# top_PCB.net
KiCad netlist of a schematic drawn in EAGLE
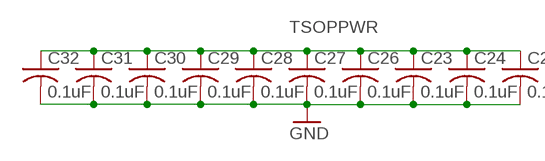
[diagram p0: schematic, sheet 1, part 1 of 2]
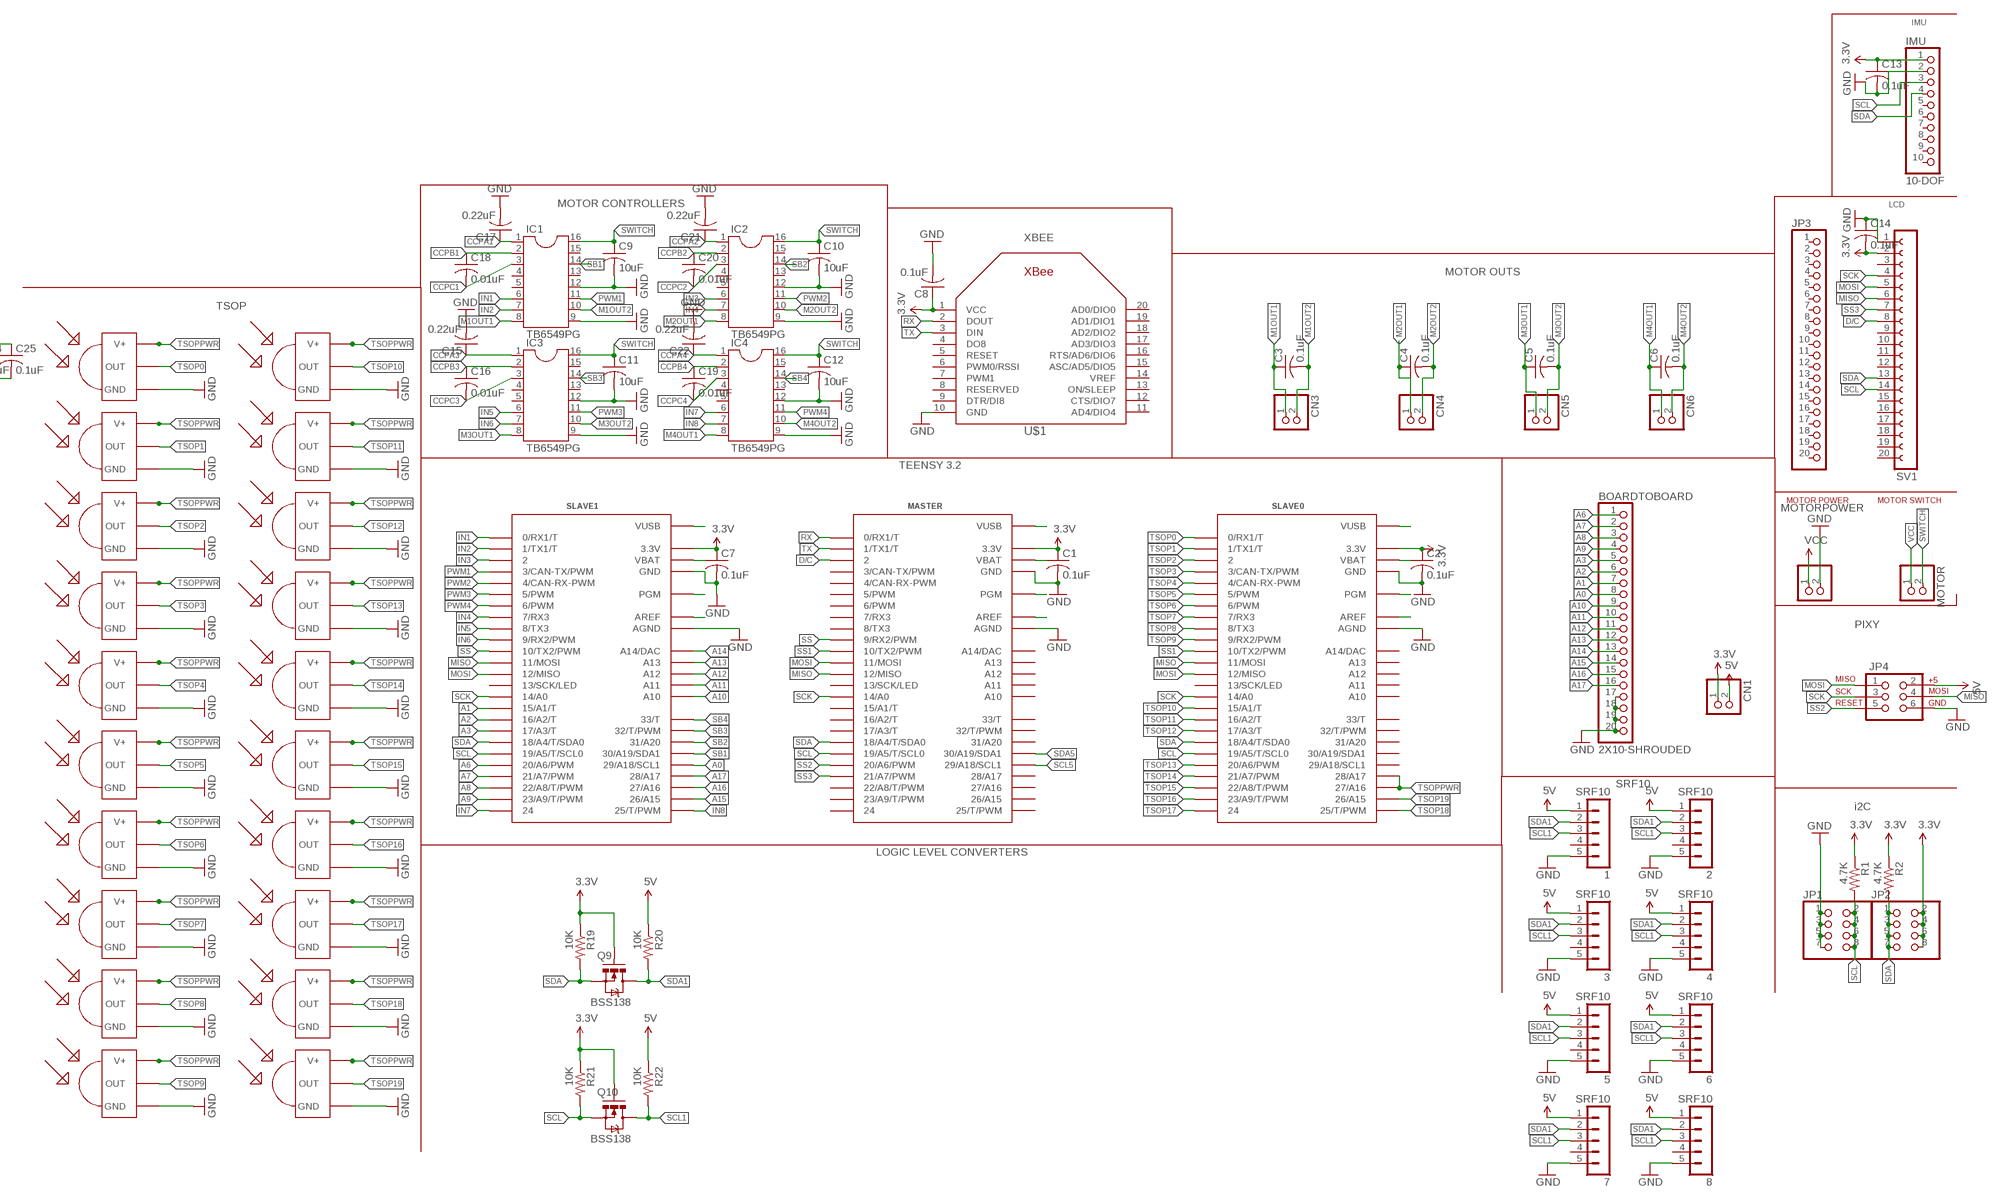
[diagram p1: schematic, sheet 1, part 2 of 2]

(export (version "E")
  (design (tool "Eeschema 10.0.6"))
  (components
    (comp (ref "1")
      (value "SRF10")
      (footprint "eagle-import:MA05-1")
      (libsource (lib "eagle-import") (part "MA05-1"))
    )
    (comp (ref "2")
      (value "SRF10")
      (footprint "eagle-import:MA05-1")
      (libsource (lib "eagle-import") (part "MA05-1"))
    )
    (comp (ref "3")
      (value "SRF10")
      (footprint "eagle-import:MA05-1")
      (libsource (lib "eagle-import") (part "MA05-1"))
    )
    (comp (ref "4")
      (value "SRF10")
      (footprint "eagle-import:MA05-1")
      (libsource (lib "eagle-import") (part "MA05-1"))
    )
    (comp (ref "5")
      (value "SRF10")
      (footprint "eagle-import:MA05-1")
      (libsource (lib "eagle-import") (part "MA05-1"))
    )
    (comp (ref "6")
      (value "SRF10")
      (footprint "eagle-import:MA05-1")
      (libsource (lib "eagle-import") (part "MA05-1"))
    )
    (comp (ref "7")
      (value "SRF10")
      (footprint "eagle-import:MA05-1")
      (libsource (lib "eagle-import") (part "MA05-1"))
    )
    (comp (ref "8")
      (value "SRF10")
      (footprint "eagle-import:MA05-1")
      (libsource (lib "eagle-import") (part "MA05-1"))
    )
    (comp (ref "BOARDTOBOARD")
      (value "2X10-SHROUDED")
      (footprint "eagle-import:2X10-SHROUDED")
      (libsource (lib "eagle-import") (part "2X10-SHROUDED"))
    )
    (comp (ref "C1")
      (value "0.1uF")
      (footprint "eagle-import:C0805")
      (libsource (lib "eagle-import") (part "C-USC0805"))
    )
    (comp (ref "C2")
      (value "0.1uF")
      (footprint "eagle-import:C0805")
      (libsource (lib "eagle-import") (part "C-USC0805"))
    )
    (comp (ref "C3")
      (value "0.1uF")
      (footprint "eagle-import:C0805")
      (libsource (lib "eagle-import") (part "C-USC0805"))
    )
    (comp (ref "C4")
      (value "0.1uF")
      (footprint "eagle-import:C0805")
      (libsource (lib "eagle-import") (part "C-USC0805"))
    )
    (comp (ref "C5")
      (value "0.1uF")
      (footprint "eagle-import:C0805")
      (libsource (lib "eagle-import") (part "C-USC0805"))
    )
    (comp (ref "C6")
      (value "0.1uF")
      (footprint "eagle-import:C0805")
      (libsource (lib "eagle-import") (part "C-USC0805"))
    )
    (comp (ref "C7")
      (value "0.1uF")
      (footprint "eagle-import:C0805")
      (libsource (lib "eagle-import") (part "C-USC0805"))
    )
    (comp (ref "C8")
      (value "0.1uF")
      (footprint "eagle-import:C0805")
      (libsource (lib "eagle-import") (part "C-USC0805"))
    )
    (comp (ref "C9")
      (value "10uF")
      (footprint "eagle-import:C0805")
      (libsource (lib "eagle-import") (part "C-USC0805"))
    )
    (comp (ref "C10")
      (value "10uF")
      (footprint "eagle-import:C0805")
      (libsource (lib "eagle-import") (part "C-USC0805"))
    )
    (comp (ref "C11")
      (value "10uF")
      (footprint "eagle-import:C0805")
      (libsource (lib "eagle-import") (part "C-USC0805"))
    )
    (comp (ref "C12")
      (value "10uF")
      (footprint "eagle-import:C0805")
      (libsource (lib "eagle-import") (part "C-USC0805"))
    )
    (comp (ref "C13")
      (value "0.1uF")
      (footprint "eagle-import:C0805")
      (libsource (lib "eagle-import") (part "C-USC0805"))
    )
    (comp (ref "C14")
      (value "0.1uF")
      (footprint "eagle-import:C0805")
      (libsource (lib "eagle-import") (part "C-USC0805"))
    )
    (comp (ref "C15")
      (value "0.22uF")
      (footprint "eagle-import:C0805")
      (libsource (lib "eagle-import") (part "C-USC0805"))
    )
    (comp (ref "C16")
      (value "0.01uF")
      (footprint "eagle-import:C0805")
      (libsource (lib "eagle-import") (part "C-USC0805"))
    )
    (comp (ref "C17")
      (value "0.22uF")
      (footprint "eagle-import:C0805")
      (libsource (lib "eagle-import") (part "C-USC0805"))
    )
    (comp (ref "C18")
      (value "0.01uF")
      (footprint "eagle-import:C0805")
      (libsource (lib "eagle-import") (part "C-USC0805"))
    )
    (comp (ref "C19")
      (value "0.01uF")
      (footprint "eagle-import:C0805")
      (libsource (lib "eagle-import") (part "C-USC0805"))
    )
    (comp (ref "C20")
      (value "0.01uF")
      (footprint "eagle-import:C0805")
      (libsource (lib "eagle-import") (part "C-USC0805"))
    )
    (comp (ref "C21")
      (value "0.22uF")
      (footprint "eagle-import:C0805")
      (libsource (lib "eagle-import") (part "C-USC0805"))
    )
    (comp (ref "C22")
      (value "0.22uF")
      (footprint "eagle-import:C0805")
      (libsource (lib "eagle-import") (part "C-USC0805"))
    )
    (comp (ref "C23")
      (value "0.1uF")
      (footprint "eagle-import:C0805")
      (libsource (lib "eagle-import") (part "C-USC0805"))
    )
    (comp (ref "C24")
      (value "0.1uF")
      (footprint "eagle-import:C0805")
      (libsource (lib "eagle-import") (part "C-USC0805"))
    )
    (comp (ref "C25")
      (value "0.1uF")
      (footprint "eagle-import:C0805")
      (libsource (lib "eagle-import") (part "C-USC0805"))
    )
    (comp (ref "C26")
      (value "0.1uF")
      (footprint "eagle-import:C0805")
      (libsource (lib "eagle-import") (part "C-USC0805"))
    )
    (comp (ref "C27")
      (value "0.1uF")
      (footprint "eagle-import:C0805")
      (libsource (lib "eagle-import") (part "C-USC0805"))
    )
    (comp (ref "C28")
      (value "0.1uF")
      (footprint "eagle-import:C0805")
      (libsource (lib "eagle-import") (part "C-USC0805"))
    )
    (comp (ref "C29")
      (value "0.1uF")
      (footprint "eagle-import:C0805")
      (libsource (lib "eagle-import") (part "C-USC0805"))
    )
    (comp (ref "C30")
      (value "0.1uF")
      (footprint "eagle-import:C0805")
      (libsource (lib "eagle-import") (part "C-USC0805"))
    )
    (comp (ref "C31")
      (value "0.1uF")
      (footprint "eagle-import:C0805")
      (libsource (lib "eagle-import") (part "C-USC0805"))
    )
    (comp (ref "C32")
      (value "0.1uF")
      (footprint "eagle-import:C0805")
      (libsource (lib "eagle-import") (part "C-USC0805"))
    )
    (comp (ref "CN1")
      (value "JST_2PIN-SMT")
      (footprint "eagle-import:JST-PH-2-SMT")
      (libsource (lib "eagle-import") (part "JST_2PIN-SMT"))
    )
    (comp (ref "CN3")
      (value "JST_2PIN-SMT")
      (footprint "eagle-import:JST-PH-2-SMT")
      (libsource (lib "eagle-import") (part "JST_2PIN-SMT"))
    )
    (comp (ref "CN4")
      (value "JST_2PIN-SMT")
      (footprint "eagle-import:JST-PH-2-SMT")
      (libsource (lib "eagle-import") (part "JST_2PIN-SMT"))
    )
    (comp (ref "CN5")
      (value "JST_2PIN-SMT")
      (footprint "eagle-import:JST-PH-2-SMT")
      (libsource (lib "eagle-import") (part "JST_2PIN-SMT"))
    )
    (comp (ref "CN6")
      (value "JST_2PIN-SMT")
      (footprint "eagle-import:JST-PH-2-SMT")
      (libsource (lib "eagle-import") (part "JST_2PIN-SMT"))
    )
    (comp (ref "IC1")
      (value "TB6549PG")
      (footprint "eagle-import:DIL16")
      (libsource (lib "eagle-import") (part "DIL16"))
    )
    (comp (ref "IC2")
      (value "TB6549PG")
      (footprint "eagle-import:DIL16")
      (libsource (lib "eagle-import") (part "DIL16"))
    )
    (comp (ref "IC3")
      (value "TB6549PG")
      (footprint "eagle-import:DIL16")
      (libsource (lib "eagle-import") (part "DIL16"))
    )
    (comp (ref "IC4")
      (value "TB6549PG")
      (footprint "eagle-import:DIL16")
      (libsource (lib "eagle-import") (part "DIL16"))
    )
    (comp (ref "IMU")
      (value "10-DOF")
      (footprint "eagle-import:1X10-BIG")
      (libsource (lib "eagle-import") (part "PINHD-1X10"))
    )
    (comp (ref "JP1")
      (value "PINHD-2X4")
      (footprint "eagle-import:2X04")
      (libsource (lib "eagle-import") (part "PINHD-2X4"))
    )
    (comp (ref "JP2")
      (value "PINHD-2X4")
      (footprint "eagle-import:2X04")
      (libsource (lib "eagle-import") (part "PINHD-2X4"))
    )
    (comp (ref "JP3")
      (value "PINHD-1X20")
      (footprint "eagle-import:1X20")
      (libsource (lib "eagle-import") (part "PINHD-1X20"))
    )
    (comp (ref "JP4")
      (value "AVR_SPI_PRG_6PTH")
      (footprint "eagle-import:2X3")
      (libsource (lib "eagle-import") (part "AVR_SPI_PRG_6PTH"))
    )
    (comp (ref "MASTER")
      (value "TEENSY_3.1_ALL_PINS_AND_PADS-VIN")
      (footprint "eagle-import:TEENSY_3.1_ALLPINS-VIN")
      (libsource (lib "eagle-import") (part "TEENSY_3.1_ALL_PINS_AND_PADS-VIN"))
    )
    (comp (ref "MOTOR")
      (value "JST_2PIN-SMT")
      (footprint "eagle-import:JST-PH-2-SMT")
      (libsource (lib "eagle-import") (part "JST_2PIN-SMT"))
    )
    (comp (ref "MOTORPOWER")
      (value "JST_2PIN-SMT")
      (footprint "eagle-import:JST-PH-2-SMT")
      (libsource (lib "eagle-import") (part "JST_2PIN-SMT"))
    )
    (comp (ref "Q9")
      (value "BSS138")
      (footprint "eagle-import:SOT23-3")
      (libsource (lib "eagle-import") (part "MOSFET-NCHANNELSMD"))
    )
    (comp (ref "Q10")
      (value "BSS138")
      (footprint "eagle-import:SOT23-3")
      (libsource (lib "eagle-import") (part "MOSFET-NCHANNELSMD"))
    )
    (comp (ref "R1")
      (value "4.7K")
      (footprint "eagle-import:R0805")
      (libsource (lib "eagle-import") (part "R-US_R0805"))
    )
    (comp (ref "R2")
      (value "4.7K")
      (footprint "eagle-import:R0805")
      (libsource (lib "eagle-import") (part "R-US_R0805"))
    )
    (comp (ref "R19")
      (value "10K")
      (footprint "eagle-import:0603-RES")
      (libsource (lib "eagle-import") (part "RESISTOR0603-RES"))
    )
    (comp (ref "R20")
      (value "10K")
      (footprint "eagle-import:0603-RES")
      (libsource (lib "eagle-import") (part "RESISTOR0603-RES"))
    )
    (comp (ref "R21")
      (value "10K")
      (footprint "eagle-import:0603-RES")
      (libsource (lib "eagle-import") (part "RESISTOR0603-RES"))
    )
    (comp (ref "R22")
      (value "10K")
      (footprint "eagle-import:0603-RES")
      (libsource (lib "eagle-import") (part "RESISTOR0603-RES"))
    )
    (comp (ref "SLAVE0")
      (value "TEENSY_3.1_ALL_PINS_AND_PADS-VIN")
      (footprint "eagle-import:TEENSY_3.1_ALLPINS-VIN")
      (libsource (lib "eagle-import") (part "TEENSY_3.1_ALL_PINS_AND_PADS-VIN"))
    )
    (comp (ref "SLAVE1")
      (value "TEENSY_3.1_ALL_PINS_AND_PADS-VIN")
      (footprint "eagle-import:TEENSY_3.1_ALLPINS-VIN")
      (libsource (lib "eagle-import") (part "TEENSY_3.1_ALL_PINS_AND_PADS-VIN"))
    )
    (comp (ref "SV1")
      (value "FE20-1")
      (footprint "eagle-import:FE20")
      (libsource (lib "eagle-import") (part "FE20-1"))
    )
    (comp (ref "TSOP1")
      (value "TSOP1730")
      (footprint "eagle-import:TSOP17XX")
      (libsource (lib "eagle-import") (part "TSOP1730"))
    )
    (comp (ref "TSOP2")
      (value "TSOP1730")
      (footprint "eagle-import:TSOP17XX")
      (libsource (lib "eagle-import") (part "TSOP1730"))
    )
    (comp (ref "TSOP3")
      (value "TSOP1730")
      (footprint "eagle-import:TSOP17XX")
      (libsource (lib "eagle-import") (part "TSOP1730"))
    )
    (comp (ref "TSOP4")
      (value "TSOP1730")
      (footprint "eagle-import:TSOP17XX")
      (libsource (lib "eagle-import") (part "TSOP1730"))
    )
    (comp (ref "TSOP5")
      (value "TSOP1730")
      (footprint "eagle-import:TSOP17XX")
      (libsource (lib "eagle-import") (part "TSOP1730"))
    )
    (comp (ref "TSOP6")
      (value "TSOP1730")
      (footprint "eagle-import:TSOP17XX")
      (libsource (lib "eagle-import") (part "TSOP1730"))
    )
    (comp (ref "TSOP7")
      (value "TSOP1730")
      (footprint "eagle-import:TSOP17XX")
      (libsource (lib "eagle-import") (part "TSOP1730"))
    )
    (comp (ref "TSOP8")
      (value "TSOP1730")
      (footprint "eagle-import:TSOP17XX")
      (libsource (lib "eagle-import") (part "TSOP1730"))
    )
    (comp (ref "TSOP9")
      (value "TSOP1730")
      (footprint "eagle-import:TSOP17XX")
      (libsource (lib "eagle-import") (part "TSOP1730"))
    )
    (comp (ref "TSOP10")
      (value "TSOP1730")
      (footprint "eagle-import:TSOP17XX")
      (libsource (lib "eagle-import") (part "TSOP1730"))
    )
    (comp (ref "TSOP11")
      (value "TSOP1730")
      (footprint "eagle-import:TSOP17XX")
      (libsource (lib "eagle-import") (part "TSOP1730"))
    )
    (comp (ref "TSOP12")
      (value "TSOP1730")
      (footprint "eagle-import:TSOP17XX")
      (libsource (lib "eagle-import") (part "TSOP1730"))
    )
    (comp (ref "TSOP13")
      (value "TSOP1730")
      (footprint "eagle-import:TSOP17XX")
      (libsource (lib "eagle-import") (part "TSOP1730"))
    )
    (comp (ref "TSOP14")
      (value "TSOP1730")
      (footprint "eagle-import:TSOP17XX")
      (libsource (lib "eagle-import") (part "TSOP1730"))
    )
    (comp (ref "TSOP15")
      (value "TSOP1730")
      (footprint "eagle-import:TSOP17XX")
      (libsource (lib "eagle-import") (part "TSOP1730"))
    )
    (comp (ref "TSOP16")
      (value "TSOP1730")
      (footprint "eagle-import:TSOP17XX")
      (libsource (lib "eagle-import") (part "TSOP1730"))
    )
    (comp (ref "TSOP17")
      (value "TSOP1730")
      (footprint "eagle-import:TSOP17XX")
      (libsource (lib "eagle-import") (part "TSOP1730"))
    )
    (comp (ref "TSOP18")
      (value "TSOP1730")
      (footprint "eagle-import:TSOP17XX")
      (libsource (lib "eagle-import") (part "TSOP1730"))
    )
    (comp (ref "TSOP19")
      (value "TSOP1730")
      (footprint "eagle-import:TSOP17XX")
      (libsource (lib "eagle-import") (part "TSOP1730"))
    )
    (comp (ref "TSOP20")
      (value "TSOP1730")
      (footprint "eagle-import:TSOP17XX")
      (libsource (lib "eagle-import") (part "TSOP1730"))
    )
    (comp (ref "U$1")
      (value "XBEE")
      (footprint "eagle-import:XBEE")
      (libsource (lib "eagle-import") (part "XBEE"))
    )
  )
  (nets
    (net (code "1") (name "3.3V") (class "Default")
      (node (ref "C1") (pin "1") (pinfunction "1_1") (pintype "passive"))
      (node (ref "C13") (pin "1") (pinfunction "1_1") (pintype "passive"))
      (node (ref "C14") (pin "2") (pinfunction "2_2") (pintype "passive"))
      (node (ref "C2") (pin "1") (pinfunction "1_1") (pintype "passive"))
      (node (ref "C7") (pin "1") (pinfunction "1_1") (pintype "passive"))
      (node (ref "C8") (pin "1") (pinfunction "1_1") (pintype "passive"))
      (node (ref "CN1") (pin "1") (pinfunction "2_1") (pintype "passive"))
      (node (ref "IMU") (pin "1") (pinfunction "1_1") (pintype "passive"))
      (node (ref "JP2") (pin "2") (pinfunction "2_2") (pintype "passive"))
      (node (ref "JP2") (pin "4") (pinfunction "4_4") (pintype "passive"))
      (node (ref "JP2") (pin "6") (pinfunction "6_6") (pintype "passive"))
      (node (ref "JP2") (pin "8") (pinfunction "8_8") (pintype "passive"))
      (node (ref "MASTER") (pin "3.3V") (pinfunction "3.3V_3.3V") (pintype "power_in"))
      (node (ref "MASTER") (pin "3.3V1") (pinfunction "3.3V_3.3V1") (pintype "power_in"))
      (node (ref "MASTER") (pin "3.3V2") (pinfunction "3.3V_3.3V2") (pintype "power_in"))
      (node (ref "Q10") (pin "1") (pinfunction "G_1") (pintype "passive"))
      (node (ref "Q9") (pin "1") (pinfunction "G_1") (pintype "passive"))
      (node (ref "R1") (pin "1") (pinfunction "1_1") (pintype "passive"))
      (node (ref "R19") (pin "1") (pinfunction "1_1") (pintype "passive"))
      (node (ref "R2") (pin "1") (pinfunction "1_1") (pintype "passive"))
      (node (ref "R21") (pin "1") (pinfunction "1_1") (pintype "passive"))
      (node (ref "SLAVE0") (pin "3.3V") (pinfunction "3.3V_3.3V") (pintype "power_in"))
      (node (ref "SLAVE0") (pin "3.3V1") (pinfunction "3.3V_3.3V1") (pintype "power_in"))
      (node (ref "SLAVE0") (pin "3.3V2") (pinfunction "3.3V_3.3V2") (pintype "power_in"))
      (node (ref "SLAVE1") (pin "3.3V") (pinfunction "3.3V_3.3V") (pintype "power_in"))
      (node (ref "SLAVE1") (pin "3.3V1") (pinfunction "3.3V_3.3V1") (pintype "power_in"))
      (node (ref "SLAVE1") (pin "3.3V2") (pinfunction "3.3V_3.3V2") (pintype "power_in"))
      (node (ref "SV1") (pin "2") (pinfunction "2_2") (pintype "passive"))
      (node (ref "U$1") (pin "1") (pinfunction "VCC_1") (pintype "power_in"))
    )
    (net (code "2") (name "5V") (class "Default")
      (node (ref "1") (pin "1") (pinfunction "1_1") (pintype "passive"))
      (node (ref "2") (pin "1") (pinfunction "1_1") (pintype "passive"))
      (node (ref "3") (pin "1") (pinfunction "1_1") (pintype "passive"))
      (node (ref "4") (pin "1") (pinfunction "1_1") (pintype "passive"))
      (node (ref "5") (pin "1") (pinfunction "1_1") (pintype "passive"))
      (node (ref "6") (pin "1") (pinfunction "1_1") (pintype "passive"))
      (node (ref "7") (pin "1") (pinfunction "1_1") (pintype "passive"))
      (node (ref "8") (pin "1") (pinfunction "1_1") (pintype "passive"))
      (node (ref "CN1") (pin "2") (pinfunction "1_2") (pintype "passive"))
      (node (ref "JP4") (pin "2") (pinfunction "2_2") (pintype "passive"))
      (node (ref "R20") (pin "1") (pinfunction "1_1") (pintype "passive"))
      (node (ref "R22") (pin "1") (pinfunction "1_1") (pintype "passive"))
    )
    (net (code "3") (name "A0") (class "Default")
      (node (ref "BOARDTOBOARD") (pin "8") (pinfunction "8_8") (pintype "passive"))
      (node (ref "SLAVE1") (pin "29") (pinfunction "29/A18/SCL1_29") (pintype "bidirectional"))
    )
    (net (code "4") (name "A1") (class "Default")
      (node (ref "BOARDTOBOARD") (pin "7") (pinfunction "7_7") (pintype "passive"))
      (node (ref "SLAVE1") (pin "15/A1") (pinfunction "15/A1/T_15/A1") (pintype "bidirectional"))
    )
    (net (code "5") (name "A2") (class "Default")
      (node (ref "BOARDTOBOARD") (pin "6") (pinfunction "6_6") (pintype "passive"))
      (node (ref "SLAVE1") (pin "16/A2") (pinfunction "16/A2/T_16/A2") (pintype "bidirectional"))
    )
    (net (code "6") (name "A3") (class "Default")
      (node (ref "BOARDTOBOARD") (pin "5") (pinfunction "5_5") (pintype "passive"))
      (node (ref "SLAVE1") (pin "17/A3") (pinfunction "17/A3/T_17/A3") (pintype "bidirectional"))
    )
    (net (code "7") (name "A6") (class "Default")
      (node (ref "BOARDTOBOARD") (pin "1") (pinfunction "1_1") (pintype "passive"))
      (node (ref "SLAVE1") (pin "20/A6") (pinfunction "20/A6/PWM_20/A6") (pintype "bidirectional"))
    )
    (net (code "8") (name "A7") (class "Default")
      (node (ref "BOARDTOBOARD") (pin "2") (pinfunction "2_2") (pintype "passive"))
      (node (ref "SLAVE1") (pin "21/A7") (pinfunction "21/A7/PWM_21/A7") (pintype "bidirectional"))
    )
    (net (code "9") (name "A8") (class "Default")
      (node (ref "BOARDTOBOARD") (pin "3") (pinfunction "3_3") (pintype "passive"))
      (node (ref "SLAVE1") (pin "22/A8") (pinfunction "22/A8/T/PWM_22/A8") (pintype "bidirectional"))
    )
    (net (code "10") (name "A9") (class "Default")
      (node (ref "BOARDTOBOARD") (pin "4") (pinfunction "4_4") (pintype "passive"))
      (node (ref "SLAVE1") (pin "23/A9") (pinfunction "23/A9/T/PWM_23/A9") (pintype "bidirectional"))
    )
    (net (code "11") (name "A10") (class "Default")
      (node (ref "BOARDTOBOARD") (pin "9") (pinfunction "9_9") (pintype "passive"))
      (node (ref "SLAVE1") (pin "A10") (pinfunction "A10_A10") (pintype "bidirectional"))
    )
    (net (code "12") (name "A11") (class "Default")
      (node (ref "BOARDTOBOARD") (pin "10") (pinfunction "10_10") (pintype "passive"))
      (node (ref "SLAVE1") (pin "A11") (pinfunction "A11_A11") (pintype "bidirectional"))
    )
    (net (code "13") (name "A12") (class "Default")
      (node (ref "BOARDTOBOARD") (pin "11") (pinfunction "11_11") (pintype "passive"))
      (node (ref "SLAVE1") (pin "A12") (pinfunction "A12_A12") (pintype "bidirectional"))
    )
    (net (code "14") (name "A13") (class "Default")
      (node (ref "BOARDTOBOARD") (pin "12") (pinfunction "12_12") (pintype "passive"))
      (node (ref "SLAVE1") (pin "A13") (pinfunction "A13_A13") (pintype "bidirectional"))
    )
    (net (code "15") (name "A14") (class "Default")
      (node (ref "BOARDTOBOARD") (pin "13") (pinfunction "13_13") (pintype "passive"))
      (node (ref "SLAVE1") (pin "A14") (pinfunction "A14/DAC_A14") (pintype "bidirectional"))
    )
    (net (code "16") (name "A15") (class "Default")
      (node (ref "BOARDTOBOARD") (pin "14") (pinfunction "14_14") (pintype "passive"))
      (node (ref "SLAVE1") (pin "26") (pinfunction "26/A15_26") (pintype "bidirectional"))
    )
    (net (code "17") (name "A16") (class "Default")
      (node (ref "BOARDTOBOARD") (pin "15") (pinfunction "15_15") (pintype "passive"))
      (node (ref "SLAVE1") (pin "27") (pinfunction "27/A16_27") (pintype "bidirectional"))
    )
    (net (code "18") (name "A17") (class "Default")
      (node (ref "BOARDTOBOARD") (pin "16") (pinfunction "16_16") (pintype "passive"))
      (node (ref "SLAVE1") (pin "28") (pinfunction "28/A17_28") (pintype "bidirectional"))
    )
    (net (code "19") (name "CCPA1") (class "Default")
      (node (ref "C17") (pin "1") (pinfunction "1_1") (pintype "passive"))
      (node (ref "IC1") (pin "1") (pinfunction "1_1") (pintype "passive"))
    )
    (net (code "20") (name "CCPA2") (class "Default")
      (node (ref "C21") (pin "1") (pinfunction "1_1") (pintype "passive"))
      (node (ref "IC2") (pin "1") (pinfunction "1_1") (pintype "passive"))
    )
    (net (code "21") (name "CCPA3") (class "Default")
      (node (ref "C15") (pin "1") (pinfunction "1_1") (pintype "passive"))
      (node (ref "IC3") (pin "1") (pinfunction "1_1") (pintype "passive"))
    )
    (net (code "22") (name "CCPA4") (class "Default")
      (node (ref "C22") (pin "1") (pinfunction "1_1") (pintype "passive"))
      (node (ref "IC4") (pin "1") (pinfunction "1_1") (pintype "passive"))
    )
    (net (code "23") (name "CCPB1") (class "Default")
      (node (ref "C18") (pin "1") (pinfunction "1_1") (pintype "passive"))
      (node (ref "IC1") (pin "2") (pinfunction "2_2") (pintype "passive"))
    )
    (net (code "24") (name "CCPB2") (class "Default")
      (node (ref "C20") (pin "1") (pinfunction "1_1") (pintype "passive"))
      (node (ref "IC2") (pin "2") (pinfunction "2_2") (pintype "passive"))
    )
    (net (code "25") (name "CCPB3") (class "Default")
      (node (ref "C16") (pin "1") (pinfunction "1_1") (pintype "passive"))
      (node (ref "IC3") (pin "2") (pinfunction "2_2") (pintype "passive"))
    )
    (net (code "26") (name "CCPB4") (class "Default")
      (node (ref "C19") (pin "1") (pinfunction "1_1") (pintype "passive"))
      (node (ref "IC4") (pin "2") (pinfunction "2_2") (pintype "passive"))
    )
    (net (code "27") (name "CCPC1") (class "Default")
      (node (ref "C18") (pin "2") (pinfunction "2_2") (pintype "passive"))
      (node (ref "IC1") (pin "3") (pinfunction "3_3") (pintype "passive"))
    )
    (net (code "28") (name "CCPC2") (class "Default")
      (node (ref "C20") (pin "2") (pinfunction "2_2") (pintype "passive"))
      (node (ref "IC2") (pin "3") (pinfunction "3_3") (pintype "passive"))
    )
    (net (code "29") (name "CCPC3") (class "Default")
      (node (ref "C16") (pin "2") (pinfunction "2_2") (pintype "passive"))
      (node (ref "IC3") (pin "3") (pinfunction "3_3") (pintype "passive"))
    )
    (net (code "30") (name "CCPC4") (class "Default")
      (node (ref "C19") (pin "2") (pinfunction "2_2") (pintype "passive"))
      (node (ref "IC4") (pin "3") (pinfunction "3_3") (pintype "passive"))
    )
    (net (code "31") (name "D{slash}C") (class "Default")
      (node (ref "MASTER") (pin "2") (pinfunction "2_2") (pintype "bidirectional"))
      (node (ref "SV1") (pin "8") (pinfunction "8_8") (pintype "passive"))
    )
    (net (code "32") (name "GND") (class "Default")
      (node (ref "1") (pin "5") (pinfunction "5_5") (pintype "passive"))
      (node (ref "2") (pin "5") (pinfunction "5_5") (pintype "passive"))
      (node (ref "3") (pin "5") (pinfunction "5_5") (pintype "passive"))
      (node (ref "4") (pin "5") (pinfunction "5_5") (pintype "passive"))
      (node (ref "5") (pin "5") (pinfunction "5_5") (pintype "passive"))
      (node (ref "6") (pin "5") (pinfunction "5_5") (pintype "passive"))
      (node (ref "7") (pin "5") (pinfunction "5_5") (pintype "passive"))
      (node (ref "8") (pin "5") (pinfunction "5_5") (pintype "passive"))
      (node (ref "BOARDTOBOARD") (pin "17") (pinfunction "17_17") (pintype "passive"))
      (node (ref "BOARDTOBOARD") (pin "18") (pinfunction "18_18") (pintype "passive"))
      (node (ref "BOARDTOBOARD") (pin "19") (pinfunction "19_19") (pintype "passive"))
      (node (ref "BOARDTOBOARD") (pin "20") (pinfunction "20_20") (pintype "passive"))
      (node (ref "C1") (pin "2") (pinfunction "2_2") (pintype "passive"))
      (node (ref "C10") (pin "2") (pinfunction "2_2") (pintype "passive"))
      (node (ref "C11") (pin "2") (pinfunction "2_2") (pintype "passive"))
      (node (ref "C12") (pin "2") (pinfunction "2_2") (pintype "passive"))
      (node (ref "C13") (pin "2") (pinfunction "2_2") (pintype "passive"))
      (node (ref "C14") (pin "1") (pinfunction "1_1") (pintype "passive"))
      (node (ref "C15") (pin "2") (pinfunction "2_2") (pintype "passive"))
      (node (ref "C17") (pin "2") (pinfunction "2_2") (pintype "passive"))
      (node (ref "C2") (pin "2") (pinfunction "2_2") (pintype "passive"))
      (node (ref "C21") (pin "2") (pinfunction "2_2") (pintype "passive"))
      (node (ref "C22") (pin "2") (pinfunction "2_2") (pintype "passive"))
      (node (ref "C23") (pin "2") (pinfunction "2_2") (pintype "passive"))
      (node (ref "C24") (pin "2") (pinfunction "2_2") (pintype "passive"))
      (node (ref "C25") (pin "2") (pinfunction "2_2") (pintype "passive"))
      (node (ref "C26") (pin "2") (pinfunction "2_2") (pintype "passive"))
      (node (ref "C27") (pin "2") (pinfunction "2_2") (pintype "passive"))
      (node (ref "C28") (pin "2") (pinfunction "2_2") (pintype "passive"))
      (node (ref "C29") (pin "2") (pinfunction "2_2") (pintype "passive"))
      (node (ref "C30") (pin "2") (pinfunction "2_2") (pintype "passive"))
      (node (ref "C31") (pin "2") (pinfunction "2_2") (pintype "passive"))
      (node (ref "C32") (pin "2") (pinfunction "2_2") (pintype "passive"))
      (node (ref "C7") (pin "2") (pinfunction "2_2") (pintype "passive"))
      (node (ref "C8") (pin "2") (pinfunction "2_2") (pintype "passive"))
      (node (ref "C9") (pin "2") (pinfunction "2_2") (pintype "passive"))
      (node (ref "IC1") (pin "12") (pinfunction "12_12") (pintype "passive"))
      (node (ref "IC1") (pin "9") (pinfunction "9_9") (pintype "passive"))
      (node (ref "IC2") (pin "12") (pinfunction "12_12") (pintype "passive"))
      (node (ref "IC2") (pin "9") (pinfunction "9_9") (pintype "passive"))
      (node (ref "IC3") (pin "12") (pinfunction "12_12") (pintype "passive"))
      (node (ref "IC3") (pin "9") (pinfunction "9_9") (pintype "passive"))
      (node (ref "IC4") (pin "12") (pinfunction "12_12") (pintype "passive"))
      (node (ref "IC4") (pin "9") (pinfunction "9_9") (pintype "passive"))
      (node (ref "IMU") (pin "2") (pinfunction "2_2") (pintype "passive"))
      (node (ref "JP1") (pin "1") (pinfunction "1_1") (pintype "passive"))
      (node (ref "JP1") (pin "3") (pinfunction "3_3") (pintype "passive"))
      (node (ref "JP1") (pin "5") (pinfunction "5_5") (pintype "passive"))
      (node (ref "JP1") (pin "7") (pinfunction "7_7") (pintype "passive"))
      (node (ref "JP4") (pin "6") (pinfunction "6_6") (pintype "passive"))
      (node (ref "MASTER") (pin "AGND") (pinfunction "AGND_AGND") (pintype "power_in"))
      (node (ref "MASTER") (pin "GND") (pinfunction "GND_GND") (pintype "power_in"))
      (node (ref "MASTER") (pin "GND1") (pinfunction "GND_GND1") (pintype "power_in"))
      (node (ref "MASTER") (pin "GND2") (pinfunction "GND_GND2") (pintype "power_in"))
      (node (ref "MOTORPOWER") (pin "2") (pinfunction "1_2") (pintype "passive"))
      (node (ref "SLAVE0") (pin "AGND") (pinfunction "AGND_AGND") (pintype "power_in"))
      (node (ref "SLAVE0") (pin "GND") (pinfunction "GND_GND") (pintype "power_in"))
      (node (ref "SLAVE0") (pin "GND1") (pinfunction "GND_GND1") (pintype "power_in"))
      (node (ref "SLAVE0") (pin "GND2") (pinfunction "GND_GND2") (pintype "power_in"))
      (node (ref "SLAVE1") (pin "AGND") (pinfunction "AGND_AGND") (pintype "power_in"))
      (node (ref "SLAVE1") (pin "GND") (pinfunction "GND_GND") (pintype "power_in"))
      (node (ref "SLAVE1") (pin "GND1") (pinfunction "GND_GND1") (pintype "power_in"))
      (node (ref "SLAVE1") (pin "GND2") (pinfunction "GND_GND2") (pintype "power_in"))
      (node (ref "SV1") (pin "1") (pinfunction "1_1") (pintype "passive"))
      (node (ref "TSOP1") (pin "GND") (pinfunction "GND_GND") (pintype "bidirectional"))
      (node (ref "TSOP10") (pin "GND") (pinfunction "GND_GND") (pintype "bidirectional"))
      (node (ref "TSOP11") (pin "GND") (pinfunction "GND_GND") (pintype "bidirectional"))
      (node (ref "TSOP12") (pin "GND") (pinfunction "GND_GND") (pintype "bidirectional"))
      (node (ref "TSOP13") (pin "GND") (pinfunction "GND_GND") (pintype "bidirectional"))
      (node (ref "TSOP14") (pin "GND") (pinfunction "GND_GND") (pintype "bidirectional"))
      (node (ref "TSOP15") (pin "GND") (pinfunction "GND_GND") (pintype "bidirectional"))
      (node (ref "TSOP16") (pin "GND") (pinfunction "GND_GND") (pintype "bidirectional"))
      (node (ref "TSOP17") (pin "GND") (pinfunction "GND_GND") (pintype "bidirectional"))
      (node (ref "TSOP18") (pin "GND") (pinfunction "GND_GND") (pintype "bidirectional"))
      (node (ref "TSOP19") (pin "GND") (pinfunction "GND_GND") (pintype "bidirectional"))
      (node (ref "TSOP2") (pin "GND") (pinfunction "GND_GND") (pintype "bidirectional"))
      (node (ref "TSOP20") (pin "GND") (pinfunction "GND_GND") (pintype "bidirectional"))
      (node (ref "TSOP3") (pin "GND") (pinfunction "GND_GND") (pintype "bidirectional"))
      (node (ref "TSOP4") (pin "GND") (pinfunction "GND_GND") (pintype "bidirectional"))
      (node (ref "TSOP5") (pin "GND") (pinfunction "GND_GND") (pintype "bidirectional"))
      (node (ref "TSOP6") (pin "GND") (pinfunction "GND_GND") (pintype "bidirectional"))
      (node (ref "TSOP7") (pin "GND") (pinfunction "GND_GND") (pintype "bidirectional"))
      (node (ref "TSOP8") (pin "GND") (pinfunction "GND_GND") (pintype "bidirectional"))
      (node (ref "TSOP9") (pin "GND") (pinfunction "GND_GND") (pintype "bidirectional"))
      (node (ref "U$1") (pin "10") (pinfunction "GND_10") (pintype "power_in"))
    )
    (net (code "33") (name "IN1") (class "Default")
      (node (ref "IC1") (pin "6") (pinfunction "6_6") (pintype "passive"))
      (node (ref "SLAVE1") (pin "0") (pinfunction "0/RX1/T_0") (pintype "bidirectional"))
    )
    (net (code "34") (name "IN2") (class "Default")
      (node (ref "IC1") (pin "7") (pinfunction "7_7") (pintype "passive"))
      (node (ref "SLAVE1") (pin "1") (pinfunction "1/TX1/T_1") (pintype "bidirectional"))
    )
    (net (code "35") (name "IN3") (class "Default")
      (node (ref "IC2") (pin "6") (pinfunction "6_6") (pintype "passive"))
      (node (ref "SLAVE1") (pin "2") (pinfunction "2_2") (pintype "bidirectional"))
    )
    (net (code "36") (name "IN4") (class "Default")
      (node (ref "IC2") (pin "7") (pinfunction "7_7") (pintype "passive"))
      (node (ref "SLAVE1") (pin "7") (pinfunction "7/RX3_7") (pintype "bidirectional"))
    )
    (net (code "37") (name "IN5") (class "Default")
      (node (ref "IC3") (pin "6") (pinfunction "6_6") (pintype "passive"))
      (node (ref "SLAVE1") (pin "8") (pinfunction "8/TX3_8") (pintype "bidirectional"))
    )
    (net (code "38") (name "IN6") (class "Default")
      (node (ref "IC3") (pin "7") (pinfunction "7_7") (pintype "passive"))
      (node (ref "SLAVE1") (pin "9") (pinfunction "9/RX2/PWM_9") (pintype "bidirectional"))
    )
    (net (code "39") (name "IN7") (class "Default")
      (node (ref "IC4") (pin "6") (pinfunction "6_6") (pintype "passive"))
      (node (ref "SLAVE1") (pin "24") (pinfunction "24_24") (pintype "bidirectional"))
    )
    (net (code "40") (name "IN8") (class "Default")
      (node (ref "IC4") (pin "7") (pinfunction "7_7") (pintype "passive"))
      (node (ref "SLAVE1") (pin "25") (pinfunction "25/T/PWM_25") (pintype "bidirectional"))
    )
    (net (code "41") (name "M1OUT1") (class "Default")
      (node (ref "C3") (pin "1") (pinfunction "1_1") (pintype "passive"))
      (node (ref "CN3") (pin "1") (pinfunction "2_1") (pintype "passive"))
      (node (ref "IC1") (pin "8") (pinfunction "8_8") (pintype "passive"))
    )
    (net (code "42") (name "M1OUT2") (class "Default")
      (node (ref "C3") (pin "2") (pinfunction "2_2") (pintype "passive"))
      (node (ref "CN3") (pin "2") (pinfunction "1_2") (pintype "passive"))
      (node (ref "IC1") (pin "10") (pinfunction "10_10") (pintype "passive"))
    )
    (net (code "43") (name "M2OUT1") (class "Default")
      (node (ref "C4") (pin "1") (pinfunction "1_1") (pintype "passive"))
      (node (ref "CN4") (pin "1") (pinfunction "2_1") (pintype "passive"))
      (node (ref "IC2") (pin "8") (pinfunction "8_8") (pintype "passive"))
    )
    (net (code "44") (name "M2OUT2") (class "Default")
      (node (ref "C4") (pin "2") (pinfunction "2_2") (pintype "passive"))
      (node (ref "CN4") (pin "2") (pinfunction "1_2") (pintype "passive"))
      (node (ref "IC2") (pin "10") (pinfunction "10_10") (pintype "passive"))
    )
    (net (code "45") (name "M3OUT1") (class "Default")
      (node (ref "C5") (pin "1") (pinfunction "1_1") (pintype "passive"))
      (node (ref "CN5") (pin "1") (pinfunction "2_1") (pintype "passive"))
      (node (ref "IC3") (pin "8") (pinfunction "8_8") (pintype "passive"))
    )
    (net (code "46") (name "M3OUT2") (class "Default")
      (node (ref "C5") (pin "2") (pinfunction "2_2") (pintype "passive"))
      (node (ref "CN5") (pin "2") (pinfunction "1_2") (pintype "passive"))
      (node (ref "IC3") (pin "10") (pinfunction "10_10") (pintype "passive"))
    )
    (net (code "47") (name "M4OUT1") (class "Default")
      (node (ref "C6") (pin "1") (pinfunction "1_1") (pintype "passive"))
      (node (ref "CN6") (pin "1") (pinfunction "2_1") (pintype "passive"))
      (node (ref "IC4") (pin "8") (pinfunction "8_8") (pintype "passive"))
    )
    (net (code "48") (name "M4OUT2") (class "Default")
      (node (ref "C6") (pin "2") (pinfunction "2_2") (pintype "passive"))
      (node (ref "CN6") (pin "2") (pinfunction "1_2") (pintype "passive"))
      (node (ref "IC4") (pin "10") (pinfunction "10_10") (pintype "passive"))
    )
    (net (code "49") (name "MISO") (class "Default")
      (node (ref "JP4") (pin "4") (pinfunction "4_4") (pintype "passive"))
      (node (ref "MASTER") (pin "12") (pinfunction "12/MISO_12") (pintype "bidirectional"))
      (node (ref "SLAVE0") (pin "11") (pinfunction "11/MOSI_11") (pintype "bidirectional"))
      (node (ref "SLAVE1") (pin "11") (pinfunction "11/MOSI_11") (pintype "bidirectional"))
      (node (ref "SV1") (pin "6") (pinfunction "6_6") (pintype "passive"))
    )
    (net (code "50") (name "MOSI") (class "Default")
      (node (ref "JP4") (pin "1") (pinfunction "1_1") (pintype "passive"))
      (node (ref "MASTER") (pin "11") (pinfunction "11/MOSI_11") (pintype "bidirectional"))
      (node (ref "SLAVE0") (pin "12") (pinfunction "12/MISO_12") (pintype "bidirectional"))
      (node (ref "SLAVE1") (pin "12") (pinfunction "12/MISO_12") (pintype "bidirectional"))
      (node (ref "SV1") (pin "5") (pinfunction "5_5") (pintype "passive"))
    )
    (net (code "51") (name "PWM1") (class "Default")
      (node (ref "IC1") (pin "11") (pinfunction "11_11") (pintype "passive"))
      (node (ref "SLAVE1") (pin "3") (pinfunction "3/CAN-TX/PWM_3") (pintype "bidirectional"))
    )
    (net (code "52") (name "PWM2") (class "Default")
      (node (ref "IC2") (pin "11") (pinfunction "11_11") (pintype "passive"))
      (node (ref "SLAVE1") (pin "4") (pinfunction "4/CAN-RX-PWM_4") (pintype "bidirectional"))
    )
    (net (code "53") (name "PWM3") (class "Default")
      (node (ref "IC3") (pin "11") (pinfunction "11_11") (pintype "passive"))
      (node (ref "SLAVE1") (pin "5") (pinfunction "5/PWM_5") (pintype "bidirectional"))
    )
    (net (code "54") (name "PWM4") (class "Default")
      (node (ref "IC4") (pin "11") (pinfunction "11_11") (pintype "passive"))
      (node (ref "SLAVE1") (pin "6") (pinfunction "6/PWM_6") (pintype "bidirectional"))
    )
    (net (code "55") (name "RX") (class "Default")
      (node (ref "MASTER") (pin "0") (pinfunction "0/RX1/T_0") (pintype "bidirectional"))
      (node (ref "U$1") (pin "2") (pinfunction "DOUT_2") (pintype "output"))
    )
    (net (code "56") (name "SB1") (class "Default")
      (node (ref "IC1") (pin "14") (pinfunction "14_14") (pintype "passive"))
      (node (ref "SLAVE1") (pin "30") (pinfunction "30/A19/SDA1_30") (pintype "bidirectional"))
    )
    (net (code "57") (name "SB2") (class "Default")
      (node (ref "IC2") (pin "14") (pinfunction "14_14") (pintype "passive"))
      (node (ref "SLAVE1") (pin "31") (pinfunction "31/A20_31") (pintype "bidirectional"))
    )
    (net (code "58") (name "SB3") (class "Default")
      (node (ref "IC3") (pin "14") (pinfunction "14_14") (pintype "passive"))
      (node (ref "SLAVE1") (pin "32") (pinfunction "32/T/PWM_32") (pintype "bidirectional"))
    )
    (net (code "59") (name "SB4") (class "Default")
      (node (ref "IC4") (pin "14") (pinfunction "14_14") (pintype "passive"))
      (node (ref "SLAVE1") (pin "33") (pinfunction "33/T_33") (pintype "bidirectional"))
    )
    (net (code "60") (name "SCK") (class "Default")
      (node (ref "JP4") (pin "3") (pinfunction "3_3") (pintype "passive"))
      (node (ref "MASTER") (pin "14/A0") (pinfunction "14/A0_14/A0") (pintype "bidirectional"))
      (node (ref "SLAVE0") (pin "14/A0") (pinfunction "14/A0_14/A0") (pintype "bidirectional"))
      (node (ref "SLAVE1") (pin "14/A0") (pinfunction "14/A0_14/A0") (pintype "bidirectional"))
      (node (ref "SV1") (pin "4") (pinfunction "4_4") (pintype "passive"))
    )
    (net (code "61") (name "SCL") (class "Default")
      (node (ref "IMU") (pin "3") (pinfunction "3_3") (pintype "passive"))
      (node (ref "JP1") (pin "2") (pinfunction "2_2") (pintype "passive"))
      (node (ref "JP1") (pin "4") (pinfunction "4_4") (pintype "passive"))
      (node (ref "JP1") (pin "6") (pinfunction "6_6") (pintype "passive"))
      (node (ref "JP1") (pin "8") (pinfunction "8_8") (pintype "passive"))
      (node (ref "MASTER") (pin "19/A5") (pinfunction "19/A5/T/SCL0_19/A5") (pintype "bidirectional"))
      (node (ref "Q10") (pin "2") (pinfunction "S_2") (pintype "passive"))
      (node (ref "R1") (pin "2") (pinfunction "2_2") (pintype "passive"))
      (node (ref "R21") (pin "2") (pinfunction "2_2") (pintype "passive"))
      (node (ref "SLAVE0") (pin "19/A5") (pinfunction "19/A5/T/SCL0_19/A5") (pintype "bidirectional"))
      (node (ref "SLAVE1") (pin "19/A5") (pinfunction "19/A5/T/SCL0_19/A5") (pintype "bidirectional"))
      (node (ref "SV1") (pin "14") (pinfunction "14_14") (pintype "passive"))
    )
    (net (code "62") (name "SCL1") (class "Default")
      (node (ref "1") (pin "3") (pinfunction "3_3") (pintype "passive"))
      (node (ref "2") (pin "3") (pinfunction "3_3") (pintype "passive"))
      (node (ref "3") (pin "3") (pinfunction "3_3") (pintype "passive"))
      (node (ref "4") (pin "3") (pinfunction "3_3") (pintype "passive"))
      (node (ref "5") (pin "3") (pinfunction "3_3") (pintype "passive"))
      (node (ref "6") (pin "3") (pinfunction "3_3") (pintype "passive"))
      (node (ref "7") (pin "3") (pinfunction "3_3") (pintype "passive"))
      (node (ref "8") (pin "3") (pinfunction "3_3") (pintype "passive"))
      (node (ref "Q10") (pin "3") (pinfunction "D_3") (pintype "passive"))
      (node (ref "R22") (pin "2") (pinfunction "2_2") (pintype "passive"))
    )
    (net (code "63") (name "SCL5") (class "Default")
      (node (ref "MASTER") (pin "29") (pinfunction "29/A18/SCL1_29") (pintype "bidirectional"))
    )
    (net (code "64") (name "SDA") (class "Default")
      (node (ref "IMU") (pin "4") (pinfunction "4_4") (pintype "passive"))
      (node (ref "JP2") (pin "1") (pinfunction "1_1") (pintype "passive"))
      (node (ref "JP2") (pin "3") (pinfunction "3_3") (pintype "passive"))
      (node (ref "JP2") (pin "5") (pinfunction "5_5") (pintype "passive"))
      (node (ref "JP2") (pin "7") (pinfunction "7_7") (pintype "passive"))
      (node (ref "MASTER") (pin "18/A4") (pinfunction "18/A4/T/SDA0_18/A4") (pintype "bidirectional"))
      (node (ref "Q9") (pin "2") (pinfunction "S_2") (pintype "passive"))
      (node (ref "R19") (pin "2") (pinfunction "2_2") (pintype "passive"))
      (node (ref "R2") (pin "2") (pinfunction "2_2") (pintype "passive"))
      (node (ref "SLAVE0") (pin "18/A4") (pinfunction "18/A4/T/SDA0_18/A4") (pintype "bidirectional"))
      (node (ref "SLAVE1") (pin "18/A4") (pinfunction "18/A4/T/SDA0_18/A4") (pintype "bidirectional"))
      (node (ref "SV1") (pin "13") (pinfunction "13_13") (pintype "passive"))
    )
    (net (code "65") (name "SDA1") (class "Default")
      (node (ref "1") (pin "2") (pinfunction "2_2") (pintype "passive"))
      (node (ref "2") (pin "2") (pinfunction "2_2") (pintype "passive"))
      (node (ref "3") (pin "2") (pinfunction "2_2") (pintype "passive"))
      (node (ref "4") (pin "2") (pinfunction "2_2") (pintype "passive"))
      (node (ref "5") (pin "2") (pinfunction "2_2") (pintype "passive"))
      (node (ref "6") (pin "2") (pinfunction "2_2") (pintype "passive"))
      (node (ref "7") (pin "2") (pinfunction "2_2") (pintype "passive"))
      (node (ref "8") (pin "2") (pinfunction "2_2") (pintype "passive"))
      (node (ref "Q9") (pin "3") (pinfunction "D_3") (pintype "passive"))
      (node (ref "R20") (pin "2") (pinfunction "2_2") (pintype "passive"))
    )
    (net (code "66") (name "SDA5") (class "Default")
      (node (ref "MASTER") (pin "30") (pinfunction "30/A19/SDA1_30") (pintype "bidirectional"))
    )
    (net (code "67") (name "SS") (class "Default")
      (node (ref "MASTER") (pin "9") (pinfunction "9/RX2/PWM_9") (pintype "bidirectional"))
      (node (ref "SLAVE1") (pin "10") (pinfunction "10/TX2/PWM_10") (pintype "bidirectional"))
    )
    (net (code "68") (name "SS1") (class "Default")
      (node (ref "MASTER") (pin "10") (pinfunction "10/TX2/PWM_10") (pintype "bidirectional"))
      (node (ref "SLAVE0") (pin "10") (pinfunction "10/TX2/PWM_10") (pintype "bidirectional"))
    )
    (net (code "69") (name "SS2") (class "Default")
      (node (ref "JP4") (pin "5") (pinfunction "5_5") (pintype "passive"))
      (node (ref "MASTER") (pin "20/A6") (pinfunction "20/A6/PWM_20/A6") (pintype "bidirectional"))
    )
    (net (code "70") (name "SS3") (class "Default")
      (node (ref "MASTER") (pin "21/A7") (pinfunction "21/A7/PWM_21/A7") (pintype "bidirectional"))
      (node (ref "SV1") (pin "7") (pinfunction "7_7") (pintype "passive"))
    )
    (net (code "71") (name "SWITCH") (class "Default")
      (node (ref "C10") (pin "1") (pinfunction "1_1") (pintype "passive"))
      (node (ref "C11") (pin "1") (pinfunction "1_1") (pintype "passive"))
      (node (ref "C12") (pin "1") (pinfunction "1_1") (pintype "passive"))
      (node (ref "C9") (pin "1") (pinfunction "1_1") (pintype "passive"))
      (node (ref "IC1") (pin "16") (pinfunction "16_16") (pintype "passive"))
      (node (ref "IC2") (pin "16") (pinfunction "16_16") (pintype "passive"))
      (node (ref "IC3") (pin "16") (pinfunction "16_16") (pintype "passive"))
      (node (ref "IC4") (pin "16") (pinfunction "16_16") (pintype "passive"))
      (node (ref "MOTOR") (pin "2") (pinfunction "1_2") (pintype "passive"))
    )
    (net (code "72") (name "TSOP0") (class "Default")
      (node (ref "SLAVE0") (pin "0") (pinfunction "0/RX1/T_0") (pintype "bidirectional"))
      (node (ref "TSOP1") (pin "OUT") (pinfunction "OUT_OUT") (pintype "bidirectional"))
    )
    (net (code "73") (name "TSOP1") (class "Default")
      (node (ref "SLAVE0") (pin "1") (pinfunction "1/TX1/T_1") (pintype "bidirectional"))
      (node (ref "TSOP2") (pin "OUT") (pinfunction "OUT_OUT") (pintype "bidirectional"))
    )
    (net (code "74") (name "TSOP2") (class "Default")
      (node (ref "SLAVE0") (pin "2") (pinfunction "2_2") (pintype "bidirectional"))
      (node (ref "TSOP3") (pin "OUT") (pinfunction "OUT_OUT") (pintype "bidirectional"))
    )
    (net (code "75") (name "TSOP3") (class "Default")
      (node (ref "SLAVE0") (pin "3") (pinfunction "3/CAN-TX/PWM_3") (pintype "bidirectional"))
      (node (ref "TSOP4") (pin "OUT") (pinfunction "OUT_OUT") (pintype "bidirectional"))
    )
    (net (code "76") (name "TSOP4") (class "Default")
      (node (ref "SLAVE0") (pin "4") (pinfunction "4/CAN-RX-PWM_4") (pintype "bidirectional"))
      (node (ref "TSOP5") (pin "OUT") (pinfunction "OUT_OUT") (pintype "bidirectional"))
    )
    (net (code "77") (name "TSOP5") (class "Default")
      (node (ref "SLAVE0") (pin "5") (pinfunction "5/PWM_5") (pintype "bidirectional"))
      (node (ref "TSOP6") (pin "OUT") (pinfunction "OUT_OUT") (pintype "bidirectional"))
    )
    (net (code "78") (name "TSOP6") (class "Default")
      (node (ref "SLAVE0") (pin "6") (pinfunction "6/PWM_6") (pintype "bidirectional"))
      (node (ref "TSOP7") (pin "OUT") (pinfunction "OUT_OUT") (pintype "bidirectional"))
    )
    (net (code "79") (name "TSOP7") (class "Default")
      (node (ref "SLAVE0") (pin "7") (pinfunction "7/RX3_7") (pintype "bidirectional"))
      (node (ref "TSOP8") (pin "OUT") (pinfunction "OUT_OUT") (pintype "bidirectional"))
    )
    (net (code "80") (name "TSOP8") (class "Default")
      (node (ref "SLAVE0") (pin "8") (pinfunction "8/TX3_8") (pintype "bidirectional"))
      (node (ref "TSOP9") (pin "OUT") (pinfunction "OUT_OUT") (pintype "bidirectional"))
    )
    (net (code "81") (name "TSOP9") (class "Default")
      (node (ref "SLAVE0") (pin "9") (pinfunction "9/RX2/PWM_9") (pintype "bidirectional"))
      (node (ref "TSOP10") (pin "OUT") (pinfunction "OUT_OUT") (pintype "bidirectional"))
    )
    (net (code "82") (name "TSOP10") (class "Default")
      (node (ref "SLAVE0") (pin "15/A1") (pinfunction "15/A1/T_15/A1") (pintype "bidirectional"))
      (node (ref "TSOP11") (pin "OUT") (pinfunction "OUT_OUT") (pintype "bidirectional"))
    )
    (net (code "83") (name "TSOP11") (class "Default")
      (node (ref "SLAVE0") (pin "16/A2") (pinfunction "16/A2/T_16/A2") (pintype "bidirectional"))
      (node (ref "TSOP12") (pin "OUT") (pinfunction "OUT_OUT") (pintype "bidirectional"))
    )
    (net (code "84") (name "TSOP12") (class "Default")
      (node (ref "SLAVE0") (pin "17/A3") (pinfunction "17/A3/T_17/A3") (pintype "bidirectional"))
      (node (ref "TSOP13") (pin "OUT") (pinfunction "OUT_OUT") (pintype "bidirectional"))
    )
    (net (code "85") (name "TSOP13") (class "Default")
      (node (ref "SLAVE0") (pin "20/A6") (pinfunction "20/A6/PWM_20/A6") (pintype "bidirectional"))
      (node (ref "TSOP14") (pin "OUT") (pinfunction "OUT_OUT") (pintype "bidirectional"))
    )
    (net (code "86") (name "TSOP14") (class "Default")
      (node (ref "SLAVE0") (pin "21/A7") (pinfunction "21/A7/PWM_21/A7") (pintype "bidirectional"))
      (node (ref "TSOP15") (pin "OUT") (pinfunction "OUT_OUT") (pintype "bidirectional"))
    )
    (net (code "87") (name "TSOP15") (class "Default")
      (node (ref "SLAVE0") (pin "22/A8") (pinfunction "22/A8/T/PWM_22/A8") (pintype "bidirectional"))
      (node (ref "TSOP16") (pin "OUT") (pinfunction "OUT_OUT") (pintype "bidirectional"))
    )
    (net (code "88") (name "TSOP16") (class "Default")
      (node (ref "SLAVE0") (pin "23/A9") (pinfunction "23/A9/T/PWM_23/A9") (pintype "bidirectional"))
      (node (ref "TSOP17") (pin "OUT") (pinfunction "OUT_OUT") (pintype "bidirectional"))
    )
    (net (code "89") (name "TSOP17") (class "Default")
      (node (ref "SLAVE0") (pin "24") (pinfunction "24_24") (pintype "bidirectional"))
      (node (ref "TSOP18") (pin "OUT") (pinfunction "OUT_OUT") (pintype "bidirectional"))
    )
    (net (code "90") (name "TSOP18") (class "Default")
      (node (ref "SLAVE0") (pin "25") (pinfunction "25/T/PWM_25") (pintype "bidirectional"))
      (node (ref "TSOP19") (pin "OUT") (pinfunction "OUT_OUT") (pintype "bidirectional"))
    )
    (net (code "91") (name "TSOP19") (class "Default")
      (node (ref "SLAVE0") (pin "26") (pinfunction "26/A15_26") (pintype "bidirectional"))
      (node (ref "TSOP20") (pin "OUT") (pinfunction "OUT_OUT") (pintype "bidirectional"))
    )
    (net (code "92") (name "TSOPPWR") (class "Default")
      (node (ref "C23") (pin "1") (pinfunction "1_1") (pintype "passive"))
      (node (ref "C24") (pin "1") (pinfunction "1_1") (pintype "passive"))
      (node (ref "C25") (pin "1") (pinfunction "1_1") (pintype "passive"))
      (node (ref "C26") (pin "1") (pinfunction "1_1") (pintype "passive"))
      (node (ref "C27") (pin "1") (pinfunction "1_1") (pintype "passive"))
      (node (ref "C28") (pin "1") (pinfunction "1_1") (pintype "passive"))
      (node (ref "C29") (pin "1") (pinfunction "1_1") (pintype "passive"))
      (node (ref "C30") (pin "1") (pinfunction "1_1") (pintype "passive"))
      (node (ref "C31") (pin "1") (pinfunction "1_1") (pintype "passive"))
      (node (ref "C32") (pin "1") (pinfunction "1_1") (pintype "passive"))
      (node (ref "SLAVE0") (pin "27") (pinfunction "27/A16_27") (pintype "bidirectional"))
      (node (ref "SLAVE0") (pin "28") (pinfunction "28/A17_28") (pintype "bidirectional"))
      (node (ref "TSOP1") (pin "V+") (pinfunction "V+_V+") (pintype "bidirectional"))
      (node (ref "TSOP10") (pin "V+") (pinfunction "V+_V+") (pintype "bidirectional"))
      (node (ref "TSOP11") (pin "V+") (pinfunction "V+_V+") (pintype "bidirectional"))
      (node (ref "TSOP12") (pin "V+") (pinfunction "V+_V+") (pintype "bidirectional"))
      (node (ref "TSOP13") (pin "V+") (pinfunction "V+_V+") (pintype "bidirectional"))
      (node (ref "TSOP14") (pin "V+") (pinfunction "V+_V+") (pintype "bidirectional"))
      (node (ref "TSOP15") (pin "V+") (pinfunction "V+_V+") (pintype "bidirectional"))
      (node (ref "TSOP16") (pin "V+") (pinfunction "V+_V+") (pintype "bidirectional"))
      (node (ref "TSOP17") (pin "V+") (pinfunction "V+_V+") (pintype "bidirectional"))
      (node (ref "TSOP18") (pin "V+") (pinfunction "V+_V+") (pintype "bidirectional"))
      (node (ref "TSOP19") (pin "V+") (pinfunction "V+_V+") (pintype "bidirectional"))
      (node (ref "TSOP2") (pin "V+") (pinfunction "V+_V+") (pintype "bidirectional"))
      (node (ref "TSOP20") (pin "V+") (pinfunction "V+_V+") (pintype "bidirectional"))
      (node (ref "TSOP3") (pin "V+") (pinfunction "V+_V+") (pintype "bidirectional"))
      (node (ref "TSOP4") (pin "V+") (pinfunction "V+_V+") (pintype "bidirectional"))
      (node (ref "TSOP5") (pin "V+") (pinfunction "V+_V+") (pintype "bidirectional"))
      (node (ref "TSOP6") (pin "V+") (pinfunction "V+_V+") (pintype "bidirectional"))
      (node (ref "TSOP7") (pin "V+") (pinfunction "V+_V+") (pintype "bidirectional"))
      (node (ref "TSOP8") (pin "V+") (pinfunction "V+_V+") (pintype "bidirectional"))
      (node (ref "TSOP9") (pin "V+") (pinfunction "V+_V+") (pintype "bidirectional"))
    )
    (net (code "93") (name "TX") (class "Default")
      (node (ref "MASTER") (pin "1") (pinfunction "1/TX1/T_1") (pintype "bidirectional"))
      (node (ref "U$1") (pin "3") (pinfunction "DIN_3") (pintype "input"))
    )
    (net (code "94") (name "VCC") (class "Default")
      (node (ref "MOTOR") (pin "1") (pinfunction "2_1") (pintype "passive"))
      (node (ref "MOTORPOWER") (pin "1") (pinfunction "2_1") (pintype "passive"))
    )
    (net (code "95") (name "unconnected-(1-Pad4)") (class "Default")
      (node (ref "1") (pin "4") (pinfunction "4_4") (pintype "passive"))
    )
    (net (code "96") (name "unconnected-(2-Pad4)") (class "Default")
      (node (ref "2") (pin "4") (pinfunction "4_4") (pintype "passive"))
    )
    (net (code "97") (name "unconnected-(3-Pad4)") (class "Default")
      (node (ref "3") (pin "4") (pinfunction "4_4") (pintype "passive"))
    )
    (net (code "98") (name "unconnected-(4-Pad4)") (class "Default")
      (node (ref "4") (pin "4") (pinfunction "4_4") (pintype "passive"))
    )
    (net (code "99") (name "unconnected-(5-Pad4)") (class "Default")
      (node (ref "5") (pin "4") (pinfunction "4_4") (pintype "passive"))
    )
    (net (code "100") (name "unconnected-(6-Pad4)") (class "Default")
      (node (ref "6") (pin "4") (pinfunction "4_4") (pintype "passive"))
    )
    (net (code "101") (name "unconnected-(7-Pad4)") (class "Default")
      (node (ref "7") (pin "4") (pinfunction "4_4") (pintype "passive"))
    )
    (net (code "102") (name "unconnected-(8-Pad4)") (class "Default")
      (node (ref "8") (pin "4") (pinfunction "4_4") (pintype "passive"))
    )
    (net (code "103") (name "unconnected-(IC1-Pad4)") (class "Default")
      (node (ref "IC1") (pin "4") (pinfunction "4_4") (pintype "passive"))
    )
    (net (code "104") (name "unconnected-(IC1-Pad5)") (class "Default")
      (node (ref "IC1") (pin "5") (pinfunction "5_5") (pintype "passive"))
    )
    (net (code "105") (name "unconnected-(IC1-Pad13)") (class "Default")
      (node (ref "IC1") (pin "13") (pinfunction "13_13") (pintype "passive"))
    )
    (net (code "106") (name "unconnected-(IC1-Pad15)") (class "Default")
      (node (ref "IC1") (pin "15") (pinfunction "15_15") (pintype "passive"))
    )
    (net (code "107") (name "unconnected-(IC2-Pad4)") (class "Default")
      (node (ref "IC2") (pin "4") (pinfunction "4_4") (pintype "passive"))
    )
    (net (code "108") (name "unconnected-(IC2-Pad5)") (class "Default")
      (node (ref "IC2") (pin "5") (pinfunction "5_5") (pintype "passive"))
    )
    (net (code "109") (name "unconnected-(IC2-Pad13)") (class "Default")
      (node (ref "IC2") (pin "13") (pinfunction "13_13") (pintype "passive"))
    )
    (net (code "110") (name "unconnected-(IC2-Pad15)") (class "Default")
      (node (ref "IC2") (pin "15") (pinfunction "15_15") (pintype "passive"))
    )
    (net (code "111") (name "unconnected-(IC3-Pad4)") (class "Default")
      (node (ref "IC3") (pin "4") (pinfunction "4_4") (pintype "passive"))
    )
    (net (code "112") (name "unconnected-(IC3-Pad5)") (class "Default")
      (node (ref "IC3") (pin "5") (pinfunction "5_5") (pintype "passive"))
    )
    (net (code "113") (name "unconnected-(IC3-Pad13)") (class "Default")
      (node (ref "IC3") (pin "13") (pinfunction "13_13") (pintype "passive"))
    )
    (net (code "114") (name "unconnected-(IC3-Pad15)") (class "Default")
      (node (ref "IC3") (pin "15") (pinfunction "15_15") (pintype "passive"))
    )
    (net (code "115") (name "unconnected-(IC4-Pad4)") (class "Default")
      (node (ref "IC4") (pin "4") (pinfunction "4_4") (pintype "passive"))
    )
    (net (code "116") (name "unconnected-(IC4-Pad5)") (class "Default")
      (node (ref "IC4") (pin "5") (pinfunction "5_5") (pintype "passive"))
    )
    (net (code "117") (name "unconnected-(IC4-Pad13)") (class "Default")
      (node (ref "IC4") (pin "13") (pinfunction "13_13") (pintype "passive"))
    )
    (net (code "118") (name "unconnected-(IC4-Pad15)") (class "Default")
      (node (ref "IC4") (pin "15") (pinfunction "15_15") (pintype "passive"))
    )
    (net (code "119") (name "unconnected-(IMU-Pad5)") (class "Default")
      (node (ref "IMU") (pin "5") (pinfunction "5_5") (pintype "passive"))
    )
    (net (code "120") (name "unconnected-(IMU-Pad6)") (class "Default")
      (node (ref "IMU") (pin "6") (pinfunction "6_6") (pintype "passive"))
    )
    (net (code "121") (name "unconnected-(IMU-Pad7)") (class "Default")
      (node (ref "IMU") (pin "7") (pinfunction "7_7") (pintype "passive"))
    )
    (net (code "122") (name "unconnected-(IMU-Pad8)") (class "Default")
      (node (ref "IMU") (pin "8") (pinfunction "8_8") (pintype "passive"))
    )
    (net (code "123") (name "unconnected-(IMU-Pad9)") (class "Default")
      (node (ref "IMU") (pin "9") (pinfunction "9_9") (pintype "passive"))
    )
    (net (code "124") (name "unconnected-(IMU-Pad10)") (class "Default")
      (node (ref "IMU") (pin "10") (pinfunction "10_10") (pintype "passive"))
    )
    (net (code "125") (name "unconnected-(JP3-Pad1)") (class "Default")
      (node (ref "JP3") (pin "1") (pinfunction "1_1") (pintype "passive"))
    )
    (net (code "126") (name "unconnected-(JP3-Pad2)") (class "Default")
      (node (ref "JP3") (pin "2") (pinfunction "2_2") (pintype "passive"))
    )
    (net (code "127") (name "unconnected-(JP3-Pad3)") (class "Default")
      (node (ref "JP3") (pin "3") (pinfunction "3_3") (pintype "passive"))
    )
    (net (code "128") (name "unconnected-(JP3-Pad4)") (class "Default")
      (node (ref "JP3") (pin "4") (pinfunction "4_4") (pintype "passive"))
    )
    (net (code "129") (name "unconnected-(JP3-Pad5)") (class "Default")
      (node (ref "JP3") (pin "5") (pinfunction "5_5") (pintype "passive"))
    )
    (net (code "130") (name "unconnected-(JP3-Pad6)") (class "Default")
      (node (ref "JP3") (pin "6") (pinfunction "6_6") (pintype "passive"))
    )
    (net (code "131") (name "unconnected-(JP3-Pad7)") (class "Default")
      (node (ref "JP3") (pin "7") (pinfunction "7_7") (pintype "passive"))
    )
    (net (code "132") (name "unconnected-(JP3-Pad8)") (class "Default")
      (node (ref "JP3") (pin "8") (pinfunction "8_8") (pintype "passive"))
    )
    (net (code "133") (name "unconnected-(JP3-Pad9)") (class "Default")
      (node (ref "JP3") (pin "9") (pinfunction "9_9") (pintype "passive"))
    )
    (net (code "134") (name "unconnected-(JP3-Pad10)") (class "Default")
      (node (ref "JP3") (pin "10") (pinfunction "10_10") (pintype "passive"))
    )
    (net (code "135") (name "unconnected-(JP3-Pad11)") (class "Default")
      (node (ref "JP3") (pin "11") (pinfunction "11_11") (pintype "passive"))
    )
    (net (code "136") (name "unconnected-(JP3-Pad12)") (class "Default")
      (node (ref "JP3") (pin "12") (pinfunction "12_12") (pintype "passive"))
    )
    (net (code "137") (name "unconnected-(JP3-Pad13)") (class "Default")
      (node (ref "JP3") (pin "13") (pinfunction "13_13") (pintype "passive"))
    )
    (net (code "138") (name "unconnected-(JP3-Pad14)") (class "Default")
      (node (ref "JP3") (pin "14") (pinfunction "14_14") (pintype "passive"))
    )
    (net (code "139") (name "unconnected-(JP3-Pad15)") (class "Default")
      (node (ref "JP3") (pin "15") (pinfunction "15_15") (pintype "passive"))
    )
    (net (code "140") (name "unconnected-(JP3-Pad16)") (class "Default")
      (node (ref "JP3") (pin "16") (pinfunction "16_16") (pintype "passive"))
    )
    (net (code "141") (name "unconnected-(JP3-Pad17)") (class "Default")
      (node (ref "JP3") (pin "17") (pinfunction "17_17") (pintype "passive"))
    )
    (net (code "142") (name "unconnected-(JP3-Pad18)") (class "Default")
      (node (ref "JP3") (pin "18") (pinfunction "18_18") (pintype "passive"))
    )
    (net (code "143") (name "unconnected-(JP3-Pad19)") (class "Default")
      (node (ref "JP3") (pin "19") (pinfunction "19_19") (pintype "passive"))
    )
    (net (code "144") (name "unconnected-(JP3-Pad20)") (class "Default")
      (node (ref "JP3") (pin "20") (pinfunction "20_20") (pintype "passive"))
    )
    (net (code "145") (name "unconnected-(MASTER-3{slash}CAN-TX{slash}PWM-Pad3)") (class "Default")
      (node (ref "MASTER") (pin "3") (pinfunction "3/CAN-TX/PWM_3") (pintype "bidirectional"))
    )
    (net (code "146") (name "unconnected-(MASTER-4{slash}CAN-RX-PWM-Pad4)") (class "Default")
      (node (ref "MASTER") (pin "4") (pinfunction "4/CAN-RX-PWM_4") (pintype "bidirectional"))
    )
    (net (code "147") (name "unconnected-(MASTER-5{slash}PWM-Pad5)") (class "Default")
      (node (ref "MASTER") (pin "5") (pinfunction "5/PWM_5") (pintype "bidirectional"))
    )
    (net (code "148") (name "unconnected-(MASTER-6{slash}PWM-Pad6)") (class "Default")
      (node (ref "MASTER") (pin "6") (pinfunction "6/PWM_6") (pintype "bidirectional"))
    )
    (net (code "149") (name "unconnected-(MASTER-7{slash}RX3-Pad7)") (class "Default")
      (node (ref "MASTER") (pin "7") (pinfunction "7/RX3_7") (pintype "bidirectional"))
    )
    (net (code "150") (name "unconnected-(MASTER-8{slash}TX3-Pad8)") (class "Default")
      (node (ref "MASTER") (pin "8") (pinfunction "8/TX3_8") (pintype "bidirectional"))
    )
    (net (code "151") (name "unconnected-(MASTER-13{slash}SCK{slash}LED-Pad13)") (class "Default")
      (node (ref "MASTER") (pin "13") (pinfunction "13/SCK/LED_13") (pintype "bidirectional"))
    )
    (net (code "152") (name "unconnected-(MASTER-15{slash}A1{slash}T-Pad15{slash}A1)") (class "Default")
      (node (ref "MASTER") (pin "15/A1") (pinfunction "15/A1/T_15/A1") (pintype "bidirectional"))
    )
    (net (code "153") (name "unconnected-(MASTER-16{slash}A2{slash}T-Pad16{slash}A2)") (class "Default")
      (node (ref "MASTER") (pin "16/A2") (pinfunction "16/A2/T_16/A2") (pintype "bidirectional"))
    )
    (net (code "154") (name "unconnected-(MASTER-17{slash}A3{slash}T-Pad17{slash}A3)") (class "Default")
      (node (ref "MASTER") (pin "17/A3") (pinfunction "17/A3/T_17/A3") (pintype "bidirectional"))
    )
    (net (code "155") (name "unconnected-(MASTER-22{slash}A8{slash}T{slash}PWM-Pad22{slash}A8)") (class "Default")
      (node (ref "MASTER") (pin "22/A8") (pinfunction "22/A8/T/PWM_22/A8") (pintype "bidirectional"))
    )
    (net (code "156") (name "unconnected-(MASTER-23{slash}A9{slash}T{slash}PWM-Pad23{slash}A9)") (class "Default")
      (node (ref "MASTER") (pin "23/A9") (pinfunction "23/A9/T/PWM_23/A9") (pintype "bidirectional"))
    )
    (net (code "157") (name "unconnected-(MASTER-25{slash}T{slash}PWM-Pad25)") (class "Default")
      (node (ref "MASTER") (pin "25") (pinfunction "25/T/PWM_25") (pintype "bidirectional"))
    )
    (net (code "158") (name "unconnected-(MASTER-26{slash}A15-Pad26)") (class "Default")
      (node (ref "MASTER") (pin "26") (pinfunction "26/A15_26") (pintype "bidirectional"))
    )
    (net (code "159") (name "unconnected-(MASTER-27{slash}A16-Pad27)") (class "Default")
      (node (ref "MASTER") (pin "27") (pinfunction "27/A16_27") (pintype "bidirectional"))
    )
    (net (code "160") (name "unconnected-(MASTER-28{slash}A17-Pad28)") (class "Default")
      (node (ref "MASTER") (pin "28") (pinfunction "28/A17_28") (pintype "bidirectional"))
    )
    (net (code "161") (name "unconnected-(MASTER-31{slash}A20-Pad31)") (class "Default")
      (node (ref "MASTER") (pin "31") (pinfunction "31/A20_31") (pintype "bidirectional"))
    )
    (net (code "162") (name "unconnected-(MASTER-32{slash}T{slash}PWM-Pad32)") (class "Default")
      (node (ref "MASTER") (pin "32") (pinfunction "32/T/PWM_32") (pintype "bidirectional"))
    )
    (net (code "163") (name "unconnected-(MASTER-33{slash}T-Pad33)") (class "Default")
      (node (ref "MASTER") (pin "33") (pinfunction "33/T_33") (pintype "bidirectional"))
    )
    (net (code "164") (name "unconnected-(MASTER-A14{slash}DAC-PadA14)") (class "Default")
      (node (ref "MASTER") (pin "A14") (pinfunction "A14/DAC_A14") (pintype "bidirectional"))
    )
    (net (code "165") (name "unconnected-(MASTER-Pad24)") (class "Default")
      (node (ref "MASTER") (pin "24") (pinfunction "24_24") (pintype "bidirectional"))
    )
    (net (code "166") (name "unconnected-(MASTER-PadA10)") (class "Default")
      (node (ref "MASTER") (pin "A10") (pinfunction "A10_A10") (pintype "bidirectional"))
    )
    (net (code "167") (name "unconnected-(MASTER-PadA11)") (class "Default")
      (node (ref "MASTER") (pin "A11") (pinfunction "A11_A11") (pintype "bidirectional"))
    )
    (net (code "168") (name "unconnected-(MASTER-PadA12)") (class "Default")
      (node (ref "MASTER") (pin "A12") (pinfunction "A12_A12") (pintype "bidirectional"))
    )
    (net (code "169") (name "unconnected-(MASTER-PadA13)") (class "Default")
      (node (ref "MASTER") (pin "A13") (pinfunction "A13_A13") (pintype "bidirectional"))
    )
    (net (code "170") (name "unconnected-(MASTER-PadAREF)") (class "Default")
      (node (ref "MASTER") (pin "AREF") (pinfunction "AREF_AREF") (pintype "power_in"))
    )
    (net (code "171") (name "unconnected-(MASTER-PadPGM)") (class "Default")
      (node (ref "MASTER") (pin "PGM") (pinfunction "PGM_PGM") (pintype "bidirectional"))
    )
    (net (code "172") (name "unconnected-(MASTER-PadVBAT)") (class "Default")
      (node (ref "MASTER") (pin "VBAT") (pinfunction "VBAT_VBAT") (pintype "power_in"))
    )
    (net (code "173") (name "unconnected-(MASTER-PadVUSB)") (class "Default")
      (node (ref "MASTER") (pin "VUSB") (pinfunction "VUSB_VUSB") (pintype "power_in"))
    )
    (net (code "174") (name "unconnected-(SLAVE0-13{slash}SCK{slash}LED-Pad13)") (class "Default")
      (node (ref "SLAVE0") (pin "13") (pinfunction "13/SCK/LED_13") (pintype "bidirectional"))
    )
    (net (code "175") (name "unconnected-(SLAVE0-29{slash}A18{slash}SCL1-Pad29)") (class "Default")
      (node (ref "SLAVE0") (pin "29") (pinfunction "29/A18/SCL1_29") (pintype "bidirectional"))
    )
    (net (code "176") (name "unconnected-(SLAVE0-30{slash}A19{slash}SDA1-Pad30)") (class "Default")
      (node (ref "SLAVE0") (pin "30") (pinfunction "30/A19/SDA1_30") (pintype "bidirectional"))
    )
    (net (code "177") (name "unconnected-(SLAVE0-31{slash}A20-Pad31)") (class "Default")
      (node (ref "SLAVE0") (pin "31") (pinfunction "31/A20_31") (pintype "bidirectional"))
    )
    (net (code "178") (name "unconnected-(SLAVE0-32{slash}T{slash}PWM-Pad32)") (class "Default")
      (node (ref "SLAVE0") (pin "32") (pinfunction "32/T/PWM_32") (pintype "bidirectional"))
    )
    (net (code "179") (name "unconnected-(SLAVE0-33{slash}T-Pad33)") (class "Default")
      (node (ref "SLAVE0") (pin "33") (pinfunction "33/T_33") (pintype "bidirectional"))
    )
    (net (code "180") (name "unconnected-(SLAVE0-A14{slash}DAC-PadA14)") (class "Default")
      (node (ref "SLAVE0") (pin "A14") (pinfunction "A14/DAC_A14") (pintype "bidirectional"))
    )
    (net (code "181") (name "unconnected-(SLAVE0-PadA10)") (class "Default")
      (node (ref "SLAVE0") (pin "A10") (pinfunction "A10_A10") (pintype "bidirectional"))
    )
    (net (code "182") (name "unconnected-(SLAVE0-PadA11)") (class "Default")
      (node (ref "SLAVE0") (pin "A11") (pinfunction "A11_A11") (pintype "bidirectional"))
    )
    (net (code "183") (name "unconnected-(SLAVE0-PadA12)") (class "Default")
      (node (ref "SLAVE0") (pin "A12") (pinfunction "A12_A12") (pintype "bidirectional"))
    )
    (net (code "184") (name "unconnected-(SLAVE0-PadA13)") (class "Default")
      (node (ref "SLAVE0") (pin "A13") (pinfunction "A13_A13") (pintype "bidirectional"))
    )
    (net (code "185") (name "unconnected-(SLAVE0-PadAREF)") (class "Default")
      (node (ref "SLAVE0") (pin "AREF") (pinfunction "AREF_AREF") (pintype "power_in"))
    )
    (net (code "186") (name "unconnected-(SLAVE0-PadPGM)") (class "Default")
      (node (ref "SLAVE0") (pin "PGM") (pinfunction "PGM_PGM") (pintype "bidirectional"))
    )
    (net (code "187") (name "unconnected-(SLAVE0-PadVBAT)") (class "Default")
      (node (ref "SLAVE0") (pin "VBAT") (pinfunction "VBAT_VBAT") (pintype "power_in"))
    )
    (net (code "188") (name "unconnected-(SLAVE0-PadVUSB)") (class "Default")
      (node (ref "SLAVE0") (pin "VUSB") (pinfunction "VUSB_VUSB") (pintype "power_in"))
    )
    (net (code "189") (name "unconnected-(SLAVE1-13{slash}SCK{slash}LED-Pad13)") (class "Default")
      (node (ref "SLAVE1") (pin "13") (pinfunction "13/SCK/LED_13") (pintype "bidirectional"))
    )
    (net (code "190") (name "unconnected-(SLAVE1-PadAREF)") (class "Default")
      (node (ref "SLAVE1") (pin "AREF") (pinfunction "AREF_AREF") (pintype "power_in"))
    )
    (net (code "191") (name "unconnected-(SLAVE1-PadPGM)") (class "Default")
      (node (ref "SLAVE1") (pin "PGM") (pinfunction "PGM_PGM") (pintype "bidirectional"))
    )
    (net (code "192") (name "unconnected-(SLAVE1-PadVBAT)") (class "Default")
      (node (ref "SLAVE1") (pin "VBAT") (pinfunction "VBAT_VBAT") (pintype "power_in"))
    )
    (net (code "193") (name "unconnected-(SLAVE1-PadVUSB)") (class "Default")
      (node (ref "SLAVE1") (pin "VUSB") (pinfunction "VUSB_VUSB") (pintype "power_in"))
    )
    (net (code "194") (name "unconnected-(SV1-Pad3)") (class "Default")
      (node (ref "SV1") (pin "3") (pinfunction "3_3") (pintype "passive"))
    )
    (net (code "195") (name "unconnected-(SV1-Pad9)") (class "Default")
      (node (ref "SV1") (pin "9") (pinfunction "9_9") (pintype "passive"))
    )
    (net (code "196") (name "unconnected-(SV1-Pad10)") (class "Default")
      (node (ref "SV1") (pin "10") (pinfunction "10_10") (pintype "passive"))
    )
    (net (code "197") (name "unconnected-(SV1-Pad11)") (class "Default")
      (node (ref "SV1") (pin "11") (pinfunction "11_11") (pintype "passive"))
    )
    (net (code "198") (name "unconnected-(SV1-Pad12)") (class "Default")
      (node (ref "SV1") (pin "12") (pinfunction "12_12") (pintype "passive"))
    )
    (net (code "199") (name "unconnected-(SV1-Pad15)") (class "Default")
      (node (ref "SV1") (pin "15") (pinfunction "15_15") (pintype "passive"))
    )
    (net (code "200") (name "unconnected-(SV1-Pad16)") (class "Default")
      (node (ref "SV1") (pin "16") (pinfunction "16_16") (pintype "passive"))
    )
    (net (code "201") (name "unconnected-(SV1-Pad17)") (class "Default")
      (node (ref "SV1") (pin "17") (pinfunction "17_17") (pintype "passive"))
    )
    (net (code "202") (name "unconnected-(SV1-Pad18)") (class "Default")
      (node (ref "SV1") (pin "18") (pinfunction "18_18") (pintype "passive"))
    )
    (net (code "203") (name "unconnected-(SV1-Pad19)") (class "Default")
      (node (ref "SV1") (pin "19") (pinfunction "19_19") (pintype "passive"))
    )
    (net (code "204") (name "unconnected-(SV1-Pad20)") (class "Default")
      (node (ref "SV1") (pin "20") (pinfunction "20_20") (pintype "passive"))
    )
    (net (code "205") (name "unconnected-(U$1-AD0{slash}DIO0-Pad20)") (class "Default")
      (node (ref "U$1") (pin "20") (pinfunction "AD0/DIO0_20") (pintype "bidirectional"))
    )
    (net (code "206") (name "unconnected-(U$1-AD1{slash}DIO1-Pad19)") (class "Default")
      (node (ref "U$1") (pin "19") (pinfunction "AD1/DIO1_19") (pintype "bidirectional"))
    )
    (net (code "207") (name "unconnected-(U$1-AD2{slash}DIO2-Pad18)") (class "Default")
      (node (ref "U$1") (pin "18") (pinfunction "AD2/DIO2_18") (pintype "bidirectional"))
    )
    (net (code "208") (name "unconnected-(U$1-AD3{slash}DIO3-Pad17)") (class "Default")
      (node (ref "U$1") (pin "17") (pinfunction "AD3/DIO3_17") (pintype "bidirectional"))
    )
    (net (code "209") (name "unconnected-(U$1-AD4{slash}DIO4-Pad11)") (class "Default")
      (node (ref "U$1") (pin "11") (pinfunction "AD4/DIO4_11") (pintype "bidirectional"))
    )
    (net (code "210") (name "unconnected-(U$1-ASC{slash}AD5{slash}DIO5-Pad15)") (class "Default")
      (node (ref "U$1") (pin "15") (pinfunction "ASC/AD5/DIO5_15") (pintype "bidirectional"))
    )
    (net (code "211") (name "unconnected-(U$1-CTS{slash}DIO7-Pad12)") (class "Default")
      (node (ref "U$1") (pin "12") (pinfunction "CTS/DIO7_12") (pintype "bidirectional"))
    )
    (net (code "212") (name "unconnected-(U$1-DO8-Pad4)") (class "Default")
      (node (ref "U$1") (pin "4") (pinfunction "DO8_4") (pintype "output"))
    )
    (net (code "213") (name "unconnected-(U$1-DTR{slash}DI8-Pad9)") (class "Default")
      (node (ref "U$1") (pin "9") (pinfunction "DTR/DI8_9") (pintype "input"))
    )
    (net (code "214") (name "unconnected-(U$1-ON{slash}SLEEP-Pad13)") (class "Default")
      (node (ref "U$1") (pin "13") (pinfunction "ON/SLEEP_13") (pintype "output"))
    )
    (net (code "215") (name "unconnected-(U$1-PWM0{slash}RSSI-Pad6)") (class "Default")
      (node (ref "U$1") (pin "6") (pinfunction "PWM0/RSSI_6") (pintype "output"))
    )
    (net (code "216") (name "unconnected-(U$1-PWM1-Pad7)") (class "Default")
      (node (ref "U$1") (pin "7") (pinfunction "PWM1_7") (pintype "output"))
    )
    (net (code "217") (name "unconnected-(U$1-RESERVED-Pad8)") (class "Default")
      (node (ref "U$1") (pin "8") (pinfunction "RESERVED_8") (pintype "no_connect"))
    )
    (net (code "218") (name "unconnected-(U$1-RESET-Pad5)") (class "Default")
      (node (ref "U$1") (pin "5") (pinfunction "RESET_5") (pintype "input"))
    )
    (net (code "219") (name "unconnected-(U$1-RTS{slash}AD6{slash}DIO6-Pad16)") (class "Default")
      (node (ref "U$1") (pin "16") (pinfunction "RTS/AD6/DIO6_16") (pintype "bidirectional"))
    )
    (net (code "220") (name "unconnected-(U$1-VREF-Pad14)") (class "Default")
      (node (ref "U$1") (pin "14") (pinfunction "VREF_14") (pintype "input"))
    )
  )
)
